# lidar_node.net
KiCad netlist of a schematic drawn in EAGLE
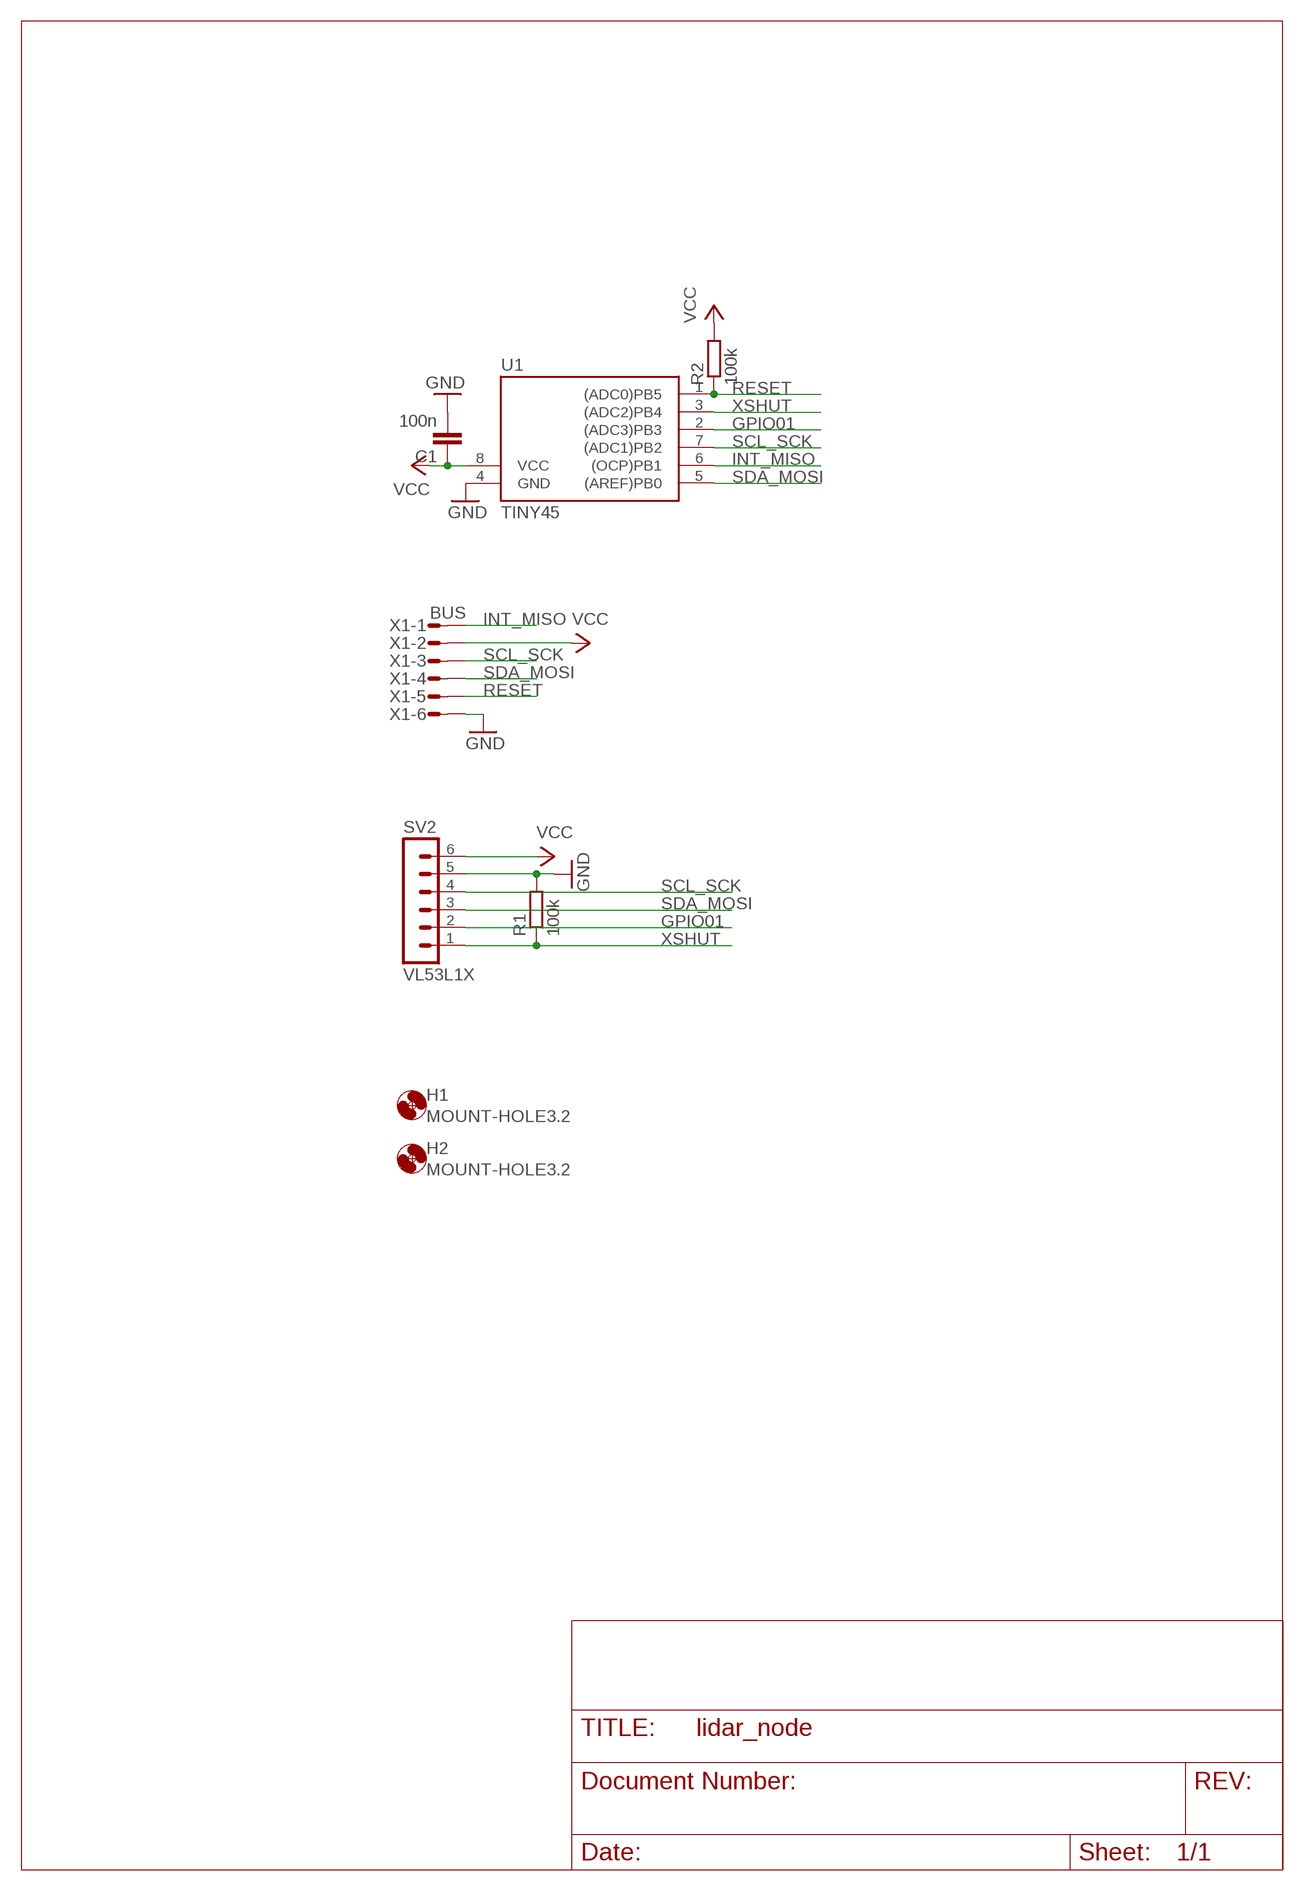
[diagram p0: schematic, sheet 1]

(export (version "E")
  (design (tool "Eeschema 10.0.6"))
  (components
    (comp (ref "C1")
      (value "100n")
      (footprint "eagle-import:C0805")
      (libsource (lib "eagle-import") (part "C-EUC0805"))
    )
    (comp (ref "H1")
      (value "MOUNT-HOLE3.2")
      (footprint "eagle-import:3,2")
      (libsource (lib "eagle-import") (part "MOUNT-HOLE3.2"))
    )
    (comp (ref "H2")
      (value "MOUNT-HOLE3.2")
      (footprint "eagle-import:3,2")
      (libsource (lib "eagle-import") (part "MOUNT-HOLE3.2"))
    )
    (comp (ref "R1")
      (value "100k")
      (footprint "eagle-import:M0805")
      (libsource (lib "eagle-import") (part "R-EU_M0805"))
    )
    (comp (ref "R2")
      (value "100k")
      (footprint "eagle-import:M0805")
      (libsource (lib "eagle-import") (part "R-EU_M0805"))
    )
    (comp (ref "SV2")
      (value "VL53L1X")
      (footprint "eagle-import:MA06-1")
      (libsource (lib "eagle-import") (part "MA06-1"))
    )
    (comp (ref "U1")
      (value "TINY45")
      (footprint "eagle-import:SOIC8")
      (libsource (lib "eagle-import") (part "TINY25/45/85-20SU"))
    )
    (comp (ref "X1")
      (value "BUS")
      (footprint "eagle-import:MICROMATCH-6")
      (fields (field (name "MPN") "7-215464-6"))
      (libsource (lib "eagle-import") (part "MICROMATCH-6"))
    )
  )
  (nets
    (net (code "1") (name "/GPIO01") (class "Default")
      (node (ref "SV2") (pin "2") (pinfunction "2_2") (pintype "passive"))
      (node (ref "U1") (pin "2") (pinfunction "(ADC3)PB3_2") (pintype "bidirectional"))
    )
    (net (code "2") (name "/INT_MISO") (class "Default")
      (node (ref "U1") (pin "6") (pinfunction "(OCP)PB1_6") (pintype "bidirectional"))
      (node (ref "X1") (pin "1") (pinfunction "S_1") (pintype "passive"))
    )
    (net (code "3") (name "/RESET") (class "Default")
      (node (ref "R2") (pin "1") (pinfunction "1_1") (pintype "passive"))
      (node (ref "U1") (pin "1") (pinfunction "(ADC0)PB5_1") (pintype "bidirectional"))
      (node (ref "X1") (pin "5") (pinfunction "S_5") (pintype "passive"))
    )
    (net (code "4") (name "/SCL_SCK") (class "Default")
      (node (ref "SV2") (pin "4") (pinfunction "4_4") (pintype "passive"))
      (node (ref "U1") (pin "7") (pinfunction "(ADC1)PB2_7") (pintype "bidirectional"))
      (node (ref "X1") (pin "3") (pinfunction "S_3") (pintype "passive"))
    )
    (net (code "5") (name "/SDA_MOSI") (class "Default")
      (node (ref "SV2") (pin "3") (pinfunction "3_3") (pintype "passive"))
      (node (ref "U1") (pin "5") (pinfunction "(AREF)PB0_5") (pintype "bidirectional"))
      (node (ref "X1") (pin "4") (pinfunction "S_4") (pintype "passive"))
    )
    (net (code "6") (name "/XSHUT") (class "Default")
      (node (ref "R1") (pin "1") (pinfunction "1_1") (pintype "passive"))
      (node (ref "SV2") (pin "1") (pinfunction "1_1") (pintype "passive"))
      (node (ref "U1") (pin "3") (pinfunction "(ADC2)PB4_3") (pintype "bidirectional"))
    )
    (net (code "7") (name "GND") (class "Default")
      (node (ref "C1") (pin "2") (pinfunction "2_2") (pintype "passive"))
      (node (ref "R1") (pin "2") (pinfunction "2_2") (pintype "passive"))
      (node (ref "SV2") (pin "5") (pinfunction "5_5") (pintype "passive"))
      (node (ref "U1") (pin "4") (pinfunction "GND_4") (pintype "power_in"))
      (node (ref "X1") (pin "6") (pinfunction "S_6") (pintype "passive"))
    )
    (net (code "8") (name "VCC") (class "Default")
      (node (ref "C1") (pin "1") (pinfunction "1_1") (pintype "passive"))
      (node (ref "R2") (pin "2") (pinfunction "2_2") (pintype "passive"))
      (node (ref "SV2") (pin "6") (pinfunction "6_6") (pintype "passive"))
      (node (ref "U1") (pin "8") (pinfunction "VCC_8") (pintype "power_in"))
      (node (ref "X1") (pin "2") (pinfunction "S_2") (pintype "passive"))
    )
  )
)
